# Connections.net
KiCad netlist of a schematic drawn in Altium Designer
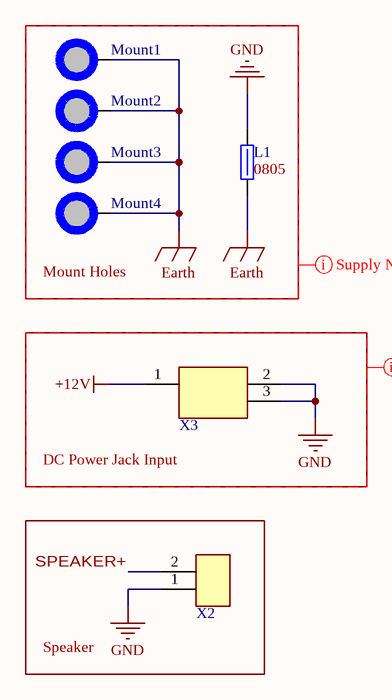
[diagram p0: Connections.SchDoc]

(export (version "E")
  (design (tool "Eeschema 10.0.6"))
  (components
    (comp (ref "L1")
      (value "652-MH2029-300Y")
      (footprint "[Ferrite] SMD 0805")
      (fields (field (name "SIZE PACKAGE") "0805"))
      (libsource (lib "Ferrite Beads") (part "[Ferrite] SMD 0805 3A 30ohm"))
    )
    (comp (ref "Mount1")
      (value "M3 Mount Hole")
      (footprint "[Mount] M3 Mount Hole")
      (description "Place at least 4.5mm from board edge. Plated.")
      (libsource (lib "Misc Components") (part "[Mount] M3 Mount Hole"))
    )
    (comp (ref "Mount2")
      (value "M3 Mount Hole")
      (footprint "[Mount] M3 Mount Hole")
      (description "Place at least 4.5mm from board edge. Plated.")
      (libsource (lib "Misc Components") (part "[Mount] M3 Mount Hole"))
    )
    (comp (ref "Mount3")
      (value "M3 Mount Hole")
      (footprint "[Mount] M3 Mount Hole")
      (description "Place at least 4.5mm from board edge. Plated.")
      (libsource (lib "Misc Components") (part "[Mount] M3 Mount Hole"))
    )
    (comp (ref "Mount4")
      (value "M3 Mount Hole")
      (footprint "[Mount] M3 Mount Hole")
      (description "Place at least 4.5mm from board edge. Plated.")
      (libsource (lib "Misc Components") (part "[Mount] M3 Mount Hole"))
    )
    (comp (ref "X2")
      (value "2pin Screw Terminal")
      (footprint "[Screw Terminal] 2pin 5mm")
      (description "TB002-500-02BE")
      (libsource (lib "Connectors") (part "[Screw Terminal] 2pin"))
    )
    (comp (ref "X3")
      (value "[Barrel] DC Jack 2mmID")
      (footprint "[Barrel] DC Jack")
      (description "PJ-102A")
      (libsource (lib "Connectors") (part "[Barrel] DC Jack 2mmID"))
    )
  )
  (nets
    (net (code "1") (name "+12V") (class "Default")
      (node (ref "X3") (pin "1") (pinfunction "Pin_1") (pintype "passive"))
    )
    (net (code "2") (name "/SPEAKER+") (class "Default") (node (ref "X2") (pin "2") (pintype "power_in")))
    (net (code "3") (name "Earth") (class "Default")
      (node (ref "L1") (pin "1") (pinfunction "1_1") (pintype "passive"))
      (node (ref "Mount1") (pin "1") (pintype "power_in"))
      (node (ref "Mount2") (pin "1") (pintype "power_in"))
      (node (ref "Mount3") (pin "1") (pintype "power_in"))
      (node (ref "Mount4") (pin "1") (pintype "power_in"))
    )
    (net (code "4") (name "GND") (class "Default")
      (node (ref "L1") (pin "2") (pinfunction "2_2") (pintype "passive"))
      (node (ref "X2") (pin "1") (pintype "power_in"))
      (node (ref "X3") (pin "2") (pinfunction "Barrel_2") (pintype "passive"))
      (node (ref "X3") (pin "3") (pinfunction "Barrel_3") (pintype "passive"))
    )
  )
)
